# Sheet1.net
KiCad netlist of a schematic drawn in Altium Designer
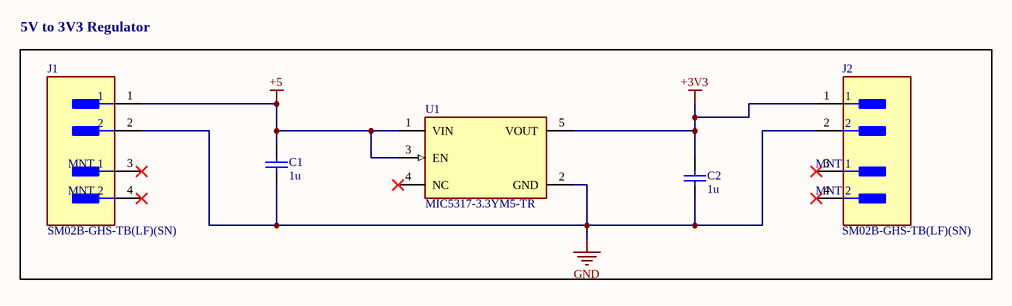
[diagram p0: Sheet1.SchDoc]

(export (version "E")
  (design (tool "Eeschema 10.0.6"))
  (components
    (comp (ref "C1")
      (value "1u")
      (footprint "CAPC2013X100X50ML20T25")
      (fields (field (name "PART NUMBER") "C0805C105K8RACTU") (field (name "MANUFACTURER") "Kemet"))
      (libsource (lib "Altium Content Vault") (part "CAP"))
    )
    (comp (ref "C2")
      (value "1u")
      (footprint "CAPC2013X100X50ML20T25")
      (fields (field (name "PART NUMBER") "C0805C105K8RACTU") (field (name "MANUFACTURER") "Kemet"))
      (libsource (lib "Altium Content Vault") (part "CAP"))
    )
    (comp (ref "J1")
      (value "SM02B-GHS-TB(LF)(SN)")
      (footprint "FP-SM02B-GHS-TB_LF_SN-MFG")
      (description "CONN HEADER SMD R/A 2POS 1.25MM")
      (libsource (lib "Altium Content Vault") (part "56ec3178a87b3978bdc1b3682cd516a"))
    )
    (comp (ref "J2")
      (value "SM02B-GHS-TB(LF)(SN)")
      (footprint "FP-SM02B-GHS-TB_LF_SN-MFG")
      (description "CONN HEADER SMD R/A 2POS 1.25MM")
      (libsource (lib "") (part "56ec3178a87b3978bdc1b3682cd516a_1"))
    )
    (comp (ref "U1")
      (value "MIC5317-3.3YM5-TR")
      (footprint "FP-SOT23-5LD-PL-1-MFG")
      (description "IC REG LINEAR 3.3V 150MA SOT23-5")
      (libsource (lib "Altium Content Vault") (part "0a093dae7315cdc977fd108dde87457"))
    )
  )
  (nets
    (net (code "1") (name "+3V3") (class "Default")
      (node (ref "C2") (pin "2") (pinfunction "2_2") (pintype "passive"))
      (node (ref "J2") (pin "1") (pinfunction "1_1") (pintype "passive"))
      (node (ref "U1") (pin "5") (pinfunction "VOUT_5") (pintype "power_in"))
    )
    (net (code "2") (name "+5") (class "Default")
      (node (ref "C1") (pin "2") (pinfunction "2_2") (pintype "passive"))
      (node (ref "J1") (pin "1") (pinfunction "1_1") (pintype "passive"))
      (node (ref "U1") (pin "1") (pinfunction "VIN_1") (pintype "power_in"))
      (node (ref "U1") (pin "3") (pinfunction "EN_3") (pintype "input"))
    )
    (net (code "3") (name "GND") (class "Default")
      (node (ref "C1") (pin "1") (pinfunction "1_1") (pintype "passive"))
      (node (ref "C2") (pin "1") (pinfunction "1_1") (pintype "passive"))
      (node (ref "J1") (pin "2") (pinfunction "2_2") (pintype "passive"))
      (node (ref "J2") (pin "2") (pinfunction "2_2") (pintype "passive"))
      (node (ref "U1") (pin "2") (pinfunction "GND_2") (pintype "power_in"))
    )
    (net (code "4") (name "unconnected-(J1-MNT_1-Pad3)") (class "Default")
      (node (ref "J1") (pin "3") (pinfunction "MNT_1_3") (pintype "passive+no_connect"))
    )
    (net (code "5") (name "unconnected-(J1-MNT_2-Pad4)") (class "Default")
      (node (ref "J1") (pin "4") (pinfunction "MNT_2_4") (pintype "passive+no_connect"))
    )
    (net (code "6") (name "unconnected-(J2-MNT_1-Pad3)") (class "Default")
      (node (ref "J2") (pin "3") (pinfunction "MNT_1_3") (pintype "passive+no_connect"))
    )
    (net (code "7") (name "unconnected-(J2-MNT_2-Pad4)") (class "Default")
      (node (ref "J2") (pin "4") (pinfunction "MNT_2_4") (pintype "passive+no_connect"))
    )
    (net (code "8") (name "unconnected-(U1-NC-Pad4)") (class "Default")
      (node (ref "U1") (pin "4") (pinfunction "NC_4") (pintype "passive+no_connect"))
    )
  )
)
